# volumes.net
KiCad netlist of a schematic drawn in Altium Designer
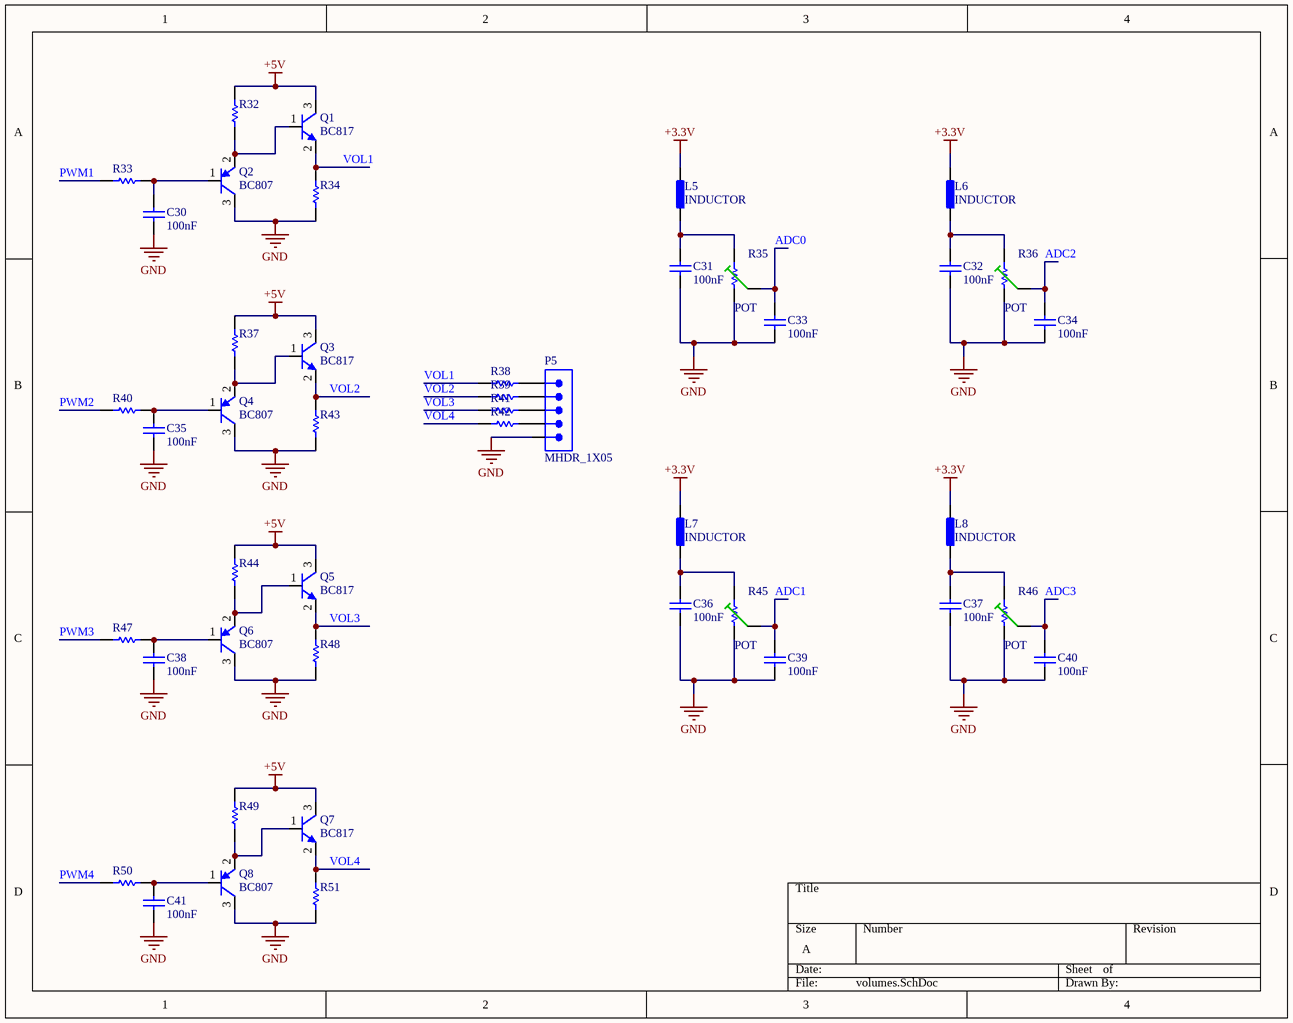
[diagram p0: volumes.SchDoc]

(export (version "E")
  (design (tool "Eeschema 10.0.6"))
  (components
    (comp (ref "C30")
      (value "100nF")
      (footprint "CAPC3216M (1206)")
      (description "Bipolar Capacitor")
      (fields
        (field (name "VOLTAGE") "100V")
        (field (name "DESIGNER") "Eng. Saeid Jorablo")
        (field (name "PUBLISHER") "SJ Unlimited")
      )
      (libsource (lib "SJ Passive Components") (part "CAP_Bipolar"))
    )
    (comp (ref "C31")
      (value "100nF")
      (footprint "CAPC3216M (1206)")
      (description "Bipolar Capacitor")
      (fields
        (field (name "VOLTAGE") "100V")
        (field (name "DESIGNER") "Eng. Saeid Jorablo")
        (field (name "PUBLISHER") "SJ Unlimited")
      )
      (libsource (lib "SJ Passive Components") (part "CAP_Bipolar"))
    )
    (comp (ref "C32")
      (value "100nF")
      (footprint "CAPC3216M (1206)")
      (description "Bipolar Capacitor")
      (fields
        (field (name "VOLTAGE") "100V")
        (field (name "DESIGNER") "Eng. Saeid Jorablo")
        (field (name "PUBLISHER") "SJ Unlimited")
      )
      (libsource (lib "SJ Passive Components") (part "CAP_Bipolar"))
    )
    (comp (ref "C33")
      (value "100nF")
      (footprint "CAPC3216M (1206)")
      (description "Bipolar Capacitor")
      (fields
        (field (name "VOLTAGE") "100V")
        (field (name "DESIGNER") "Eng. Saeid Jorablo")
        (field (name "PUBLISHER") "SJ Unlimited")
      )
      (libsource (lib "SJ Passive Components") (part "CAP_Bipolar"))
    )
    (comp (ref "C34")
      (value "100nF")
      (footprint "CAPC3216M (1206)")
      (description "Bipolar Capacitor")
      (fields
        (field (name "VOLTAGE") "100V")
        (field (name "DESIGNER") "Eng. Saeid Jorablo")
        (field (name "PUBLISHER") "SJ Unlimited")
      )
      (libsource (lib "SJ Passive Components") (part "CAP_Bipolar"))
    )
    (comp (ref "C35")
      (value "100nF")
      (footprint "CAPC3216M (1206)")
      (description "Bipolar Capacitor")
      (fields
        (field (name "VOLTAGE") "100V")
        (field (name "DESIGNER") "Eng. Saeid Jorablo")
        (field (name "PUBLISHER") "SJ Unlimited")
      )
      (libsource (lib "SJ Passive Components") (part "CAP_Bipolar"))
    )
    (comp (ref "C36")
      (value "100nF")
      (footprint "CAPC3216M (1206)")
      (description "Bipolar Capacitor")
      (fields
        (field (name "VOLTAGE") "100V")
        (field (name "DESIGNER") "Eng. Saeid Jorablo")
        (field (name "PUBLISHER") "SJ Unlimited")
      )
      (libsource (lib "SJ Passive Components") (part "CAP_Bipolar"))
    )
    (comp (ref "C37")
      (value "100nF")
      (footprint "CAPC3216M (1206)")
      (description "Bipolar Capacitor")
      (fields
        (field (name "VOLTAGE") "100V")
        (field (name "DESIGNER") "Eng. Saeid Jorablo")
        (field (name "PUBLISHER") "SJ Unlimited")
      )
      (libsource (lib "SJ Passive Components") (part "CAP_Bipolar"))
    )
    (comp (ref "C38")
      (value "100nF")
      (footprint "CAPC3216M (1206)")
      (description "Bipolar Capacitor")
      (fields
        (field (name "VOLTAGE") "100V")
        (field (name "DESIGNER") "Eng. Saeid Jorablo")
        (field (name "PUBLISHER") "SJ Unlimited")
      )
      (libsource (lib "SJ Passive Components") (part "CAP_Bipolar"))
    )
    (comp (ref "C39")
      (value "100nF")
      (footprint "CAPC3216M (1206)")
      (description "Bipolar Capacitor")
      (fields
        (field (name "VOLTAGE") "100V")
        (field (name "DESIGNER") "Eng. Saeid Jorablo")
        (field (name "PUBLISHER") "SJ Unlimited")
      )
      (libsource (lib "SJ Passive Components") (part "CAP_Bipolar"))
    )
    (comp (ref "C40")
      (value "100nF")
      (footprint "CAPC3216M (1206)")
      (description "Bipolar Capacitor")
      (fields
        (field (name "VOLTAGE") "100V")
        (field (name "DESIGNER") "Eng. Saeid Jorablo")
        (field (name "PUBLISHER") "SJ Unlimited")
      )
      (libsource (lib "SJ Passive Components") (part "CAP_Bipolar"))
    )
    (comp (ref "C41")
      (value "100nF")
      (footprint "CAPC3216M (1206)")
      (description "Bipolar Capacitor")
      (fields
        (field (name "VOLTAGE") "100V")
        (field (name "DESIGNER") "Eng. Saeid Jorablo")
        (field (name "PUBLISHER") "SJ Unlimited")
      )
      (libsource (lib "SJ Passive Components") (part "CAP_Bipolar"))
    )
    (comp (ref "L5")
      (value "INDUCTOR")
      (footprint "INDC3216")
      (description "Inductor")
      (fields (field (name "PUBLISHER") "SJ Unlimited") (field (name "DESIGNER") "Eng. Saeid Jorablo"))
      (libsource (lib "SJ Passive Components") (part "INDUCTOR"))
    )
    (comp (ref "L6")
      (value "INDUCTOR")
      (footprint "INDC3216")
      (description "Inductor")
      (fields (field (name "PUBLISHER") "SJ Unlimited") (field (name "DESIGNER") "Eng. Saeid Jorablo"))
      (libsource (lib "SJ Passive Components") (part "INDUCTOR"))
    )
    (comp (ref "L7")
      (value "INDUCTOR")
      (footprint "INDC3216")
      (description "Inductor")
      (fields (field (name "PUBLISHER") "SJ Unlimited") (field (name "DESIGNER") "Eng. Saeid Jorablo"))
      (libsource (lib "SJ Passive Components") (part "INDUCTOR"))
    )
    (comp (ref "L8")
      (value "INDUCTOR")
      (footprint "INDC3216")
      (description "Inductor")
      (fields (field (name "PUBLISHER") "SJ Unlimited") (field (name "DESIGNER") "Eng. Saeid Jorablo"))
      (libsource (lib "SJ Passive Components") (part "INDUCTOR"))
    )
    (comp (ref "P5")
      (value "MHDR_1X05")
      (footprint "MHDR1X05-254P")
      (description "Male Header 1X05")
      (libsource (lib "SJ Sockets & Connectors") (part "MHDR_1X05"))
    )
    (comp (ref "Q1")
      (value "BC817")
      (footprint "SOT23_BEC_M")
      (description "NPN Bipolar Transistor")
      (fields (field (name "PUBLISHER") "SJ Unlimited") (field (name "DESIGNER") "Eng. Saeid Jorablo"))
      (libsource (lib "SJ Passive Components") (part "NPN_BEC"))
    )
    (comp (ref "Q2")
      (value "BC807")
      (footprint "SOT23_BEC_M")
      (description "PNP Bipolar Transistor")
      (fields (field (name "PUBLISHER") "SJ Unlimited") (field (name "DESIGNER") "Eng. Saeid Jorablo"))
      (libsource (lib "SJ Passive Components") (part "PNP_BEC"))
    )
    (comp (ref "Q3")
      (value "BC817")
      (footprint "SOT23_BEC_M")
      (description "NPN Bipolar Transistor")
      (fields (field (name "PUBLISHER") "SJ Unlimited") (field (name "DESIGNER") "Eng. Saeid Jorablo"))
      (libsource (lib "SJ Passive Components") (part "NPN_BEC"))
    )
    (comp (ref "Q4")
      (value "BC807")
      (footprint "SOT23_BEC_M")
      (description "PNP Bipolar Transistor")
      (fields (field (name "PUBLISHER") "SJ Unlimited") (field (name "DESIGNER") "Eng. Saeid Jorablo"))
      (libsource (lib "SJ Passive Components") (part "PNP_BEC"))
    )
    (comp (ref "Q5")
      (value "BC817")
      (footprint "SOT23_BEC_M")
      (description "NPN Bipolar Transistor")
      (fields (field (name "PUBLISHER") "SJ Unlimited") (field (name "DESIGNER") "Eng. Saeid Jorablo"))
      (libsource (lib "SJ Passive Components") (part "NPN_BEC"))
    )
    (comp (ref "Q6")
      (value "BC807")
      (footprint "SOT23_BEC_M")
      (description "PNP Bipolar Transistor")
      (fields (field (name "PUBLISHER") "SJ Unlimited") (field (name "DESIGNER") "Eng. Saeid Jorablo"))
      (libsource (lib "SJ Passive Components") (part "PNP_BEC"))
    )
    (comp (ref "Q7")
      (value "BC817")
      (footprint "SOT23_BEC_M")
      (description "NPN Bipolar Transistor")
      (fields (field (name "PUBLISHER") "SJ Unlimited") (field (name "DESIGNER") "Eng. Saeid Jorablo"))
      (libsource (lib "SJ Passive Components") (part "NPN_BEC"))
    )
    (comp (ref "Q8")
      (value "BC807")
      (footprint "SOT23_BEC_M")
      (description "PNP Bipolar Transistor")
      (fields (field (name "PUBLISHER") "SJ Unlimited") (field (name "DESIGNER") "Eng. Saeid Jorablo"))
      (libsource (lib "SJ Passive Components") (part "PNP_BEC"))
    )
    (comp (ref "R32")
      (value "1K")
      (footprint "RESC3216X60M (1206)")
      (description "Resistor")
      (fields
        (field (name "TOLERANCE") "5%")
        (field (name "POWER") "1/8 W")
        (field (name "DESIGNER") "Eng. Saeid Jorablo")
        (field (name "PUBLISHER") "SJ Unlimited")
      )
      (libsource (lib "SJ Passive Components") (part "RES"))
    )
    (comp (ref "R33")
      (value "1K")
      (footprint "RESC3216X60M (1206)")
      (description "Resistor")
      (fields
        (field (name "TOLERANCE") "5%")
        (field (name "POWER") "1/8 W")
        (field (name "DESIGNER") "Eng. Saeid Jorablo")
        (field (name "PUBLISHER") "SJ Unlimited")
      )
      (libsource (lib "SJ Passive Components") (part "RES"))
    )
    (comp (ref "R34")
      (value "1K")
      (footprint "RESC3216X60M (1206)")
      (description "Resistor")
      (fields
        (field (name "TOLERANCE") "5%")
        (field (name "POWER") "1/8 W")
        (field (name "DESIGNER") "Eng. Saeid Jorablo")
        (field (name "PUBLISHER") "SJ Unlimited")
      )
      (libsource (lib "SJ Passive Components") (part "RES"))
    )
    (comp (ref "R35")
      (value "POT")
      (footprint "EVUF")
      (libsource (lib "SJ Passive Components") (part "RES_POT_LIN"))
    )
    (comp (ref "R36")
      (value "POT")
      (footprint "EVUF")
      (libsource (lib "SJ Passive Components") (part "RES_POT_LIN"))
    )
    (comp (ref "R37")
      (value "1K")
      (footprint "RESC3216X60M (1206)")
      (description "Resistor")
      (fields
        (field (name "TOLERANCE") "5%")
        (field (name "POWER") "1/8 W")
        (field (name "DESIGNER") "Eng. Saeid Jorablo")
        (field (name "PUBLISHER") "SJ Unlimited")
      )
      (libsource (lib "SJ Passive Components") (part "RES"))
    )
    (comp (ref "R38")
      (value "1K")
      (footprint "RESC3216X60M (1206)")
      (description "Resistor")
      (fields
        (field (name "TOLERANCE") "5%")
        (field (name "POWER") "1/8 W")
        (field (name "DESIGNER") "Eng. Saeid Jorablo")
        (field (name "PUBLISHER") "SJ Unlimited")
      )
      (libsource (lib "SJ Passive Components") (part "RES"))
    )
    (comp (ref "R39")
      (value "1K")
      (footprint "RESC3216X60M (1206)")
      (description "Resistor")
      (fields
        (field (name "TOLERANCE") "5%")
        (field (name "POWER") "1/8 W")
        (field (name "DESIGNER") "Eng. Saeid Jorablo")
        (field (name "PUBLISHER") "SJ Unlimited")
      )
      (libsource (lib "SJ Passive Components") (part "RES"))
    )
    (comp (ref "R40")
      (value "1K")
      (footprint "RESC3216X60M (1206)")
      (description "Resistor")
      (fields
        (field (name "TOLERANCE") "5%")
        (field (name "POWER") "1/8 W")
        (field (name "DESIGNER") "Eng. Saeid Jorablo")
        (field (name "PUBLISHER") "SJ Unlimited")
      )
      (libsource (lib "SJ Passive Components") (part "RES"))
    )
    (comp (ref "R41")
      (value "1K")
      (footprint "RESC3216X60M (1206)")
      (description "Resistor")
      (fields
        (field (name "TOLERANCE") "5%")
        (field (name "POWER") "1/8 W")
        (field (name "DESIGNER") "Eng. Saeid Jorablo")
        (field (name "PUBLISHER") "SJ Unlimited")
      )
      (libsource (lib "SJ Passive Components") (part "RES"))
    )
    (comp (ref "R42")
      (value "1K")
      (footprint "RESC3216X60M (1206)")
      (description "Resistor")
      (fields
        (field (name "TOLERANCE") "5%")
        (field (name "POWER") "1/8 W")
        (field (name "DESIGNER") "Eng. Saeid Jorablo")
        (field (name "PUBLISHER") "SJ Unlimited")
      )
      (libsource (lib "SJ Passive Components") (part "RES"))
    )
    (comp (ref "R43")
      (value "1K")
      (footprint "RESC3216X60M (1206)")
      (description "Resistor")
      (fields
        (field (name "TOLERANCE") "5%")
        (field (name "POWER") "1/8 W")
        (field (name "DESIGNER") "Eng. Saeid Jorablo")
        (field (name "PUBLISHER") "SJ Unlimited")
      )
      (libsource (lib "SJ Passive Components") (part "RES"))
    )
    (comp (ref "R44")
      (value "1K")
      (footprint "RESC3216X60M (1206)")
      (description "Resistor")
      (fields
        (field (name "TOLERANCE") "5%")
        (field (name "POWER") "1/8 W")
        (field (name "DESIGNER") "Eng. Saeid Jorablo")
        (field (name "PUBLISHER") "SJ Unlimited")
      )
      (libsource (lib "SJ Passive Components") (part "RES"))
    )
    (comp (ref "R45")
      (value "POT")
      (footprint "EVUF")
      (libsource (lib "SJ Passive Components") (part "RES_POT_LIN"))
    )
    (comp (ref "R46")
      (value "POT")
      (footprint "EVUF")
      (libsource (lib "SJ Passive Components") (part "RES_POT_LIN"))
    )
    (comp (ref "R47")
      (value "1K")
      (footprint "RESC3216X60M (1206)")
      (description "Resistor")
      (fields
        (field (name "TOLERANCE") "5%")
        (field (name "POWER") "1/8 W")
        (field (name "DESIGNER") "Eng. Saeid Jorablo")
        (field (name "PUBLISHER") "SJ Unlimited")
      )
      (libsource (lib "SJ Passive Components") (part "RES"))
    )
    (comp (ref "R48")
      (value "1K")
      (footprint "RESC3216X60M (1206)")
      (description "Resistor")
      (fields
        (field (name "TOLERANCE") "5%")
        (field (name "POWER") "1/8 W")
        (field (name "DESIGNER") "Eng. Saeid Jorablo")
        (field (name "PUBLISHER") "SJ Unlimited")
      )
      (libsource (lib "SJ Passive Components") (part "RES"))
    )
    (comp (ref "R49")
      (value "1K")
      (footprint "RESC3216X60M (1206)")
      (description "Resistor")
      (fields
        (field (name "TOLERANCE") "5%")
        (field (name "POWER") "1/8 W")
        (field (name "DESIGNER") "Eng. Saeid Jorablo")
        (field (name "PUBLISHER") "SJ Unlimited")
      )
      (libsource (lib "SJ Passive Components") (part "RES"))
    )
    (comp (ref "R50")
      (value "1K")
      (footprint "RESC3216X60M (1206)")
      (description "Resistor")
      (fields
        (field (name "TOLERANCE") "5%")
        (field (name "POWER") "1/8 W")
        (field (name "DESIGNER") "Eng. Saeid Jorablo")
        (field (name "PUBLISHER") "SJ Unlimited")
      )
      (libsource (lib "SJ Passive Components") (part "RES"))
    )
    (comp (ref "R51")
      (value "1K")
      (footprint "RESC3216X60M (1206)")
      (description "Resistor")
      (fields
        (field (name "TOLERANCE") "5%")
        (field (name "POWER") "1/8 W")
        (field (name "DESIGNER") "Eng. Saeid Jorablo")
        (field (name "PUBLISHER") "SJ Unlimited")
      )
      (libsource (lib "SJ Passive Components") (part "RES"))
    )
  )
  (nets
    (net (code "1") (name "+3.3V") (class "Default")
      (node (ref "L5") (pin "2") (pinfunction "2_2") (pintype "passive"))
      (node (ref "L6") (pin "2") (pinfunction "2_2") (pintype "passive"))
      (node (ref "L7") (pin "2") (pinfunction "2_2") (pintype "passive"))
      (node (ref "L8") (pin "2") (pinfunction "2_2") (pintype "passive"))
    )
    (net (code "2") (name "+5V") (class "Default")
      (node (ref "Q1") (pin "3") (pinfunction "C_3") (pintype "passive"))
      (node (ref "Q3") (pin "3") (pinfunction "C_3") (pintype "passive"))
      (node (ref "Q5") (pin "3") (pinfunction "C_3") (pintype "passive"))
      (node (ref "Q7") (pin "3") (pinfunction "C_3") (pintype "passive"))
      (node (ref "R32") (pin "1") (pinfunction "1_1") (pintype "passive"))
      (node (ref "R37") (pin "1") (pinfunction "1_1") (pintype "passive"))
      (node (ref "R44") (pin "1") (pinfunction "1_1") (pintype "passive"))
      (node (ref "R49") (pin "1") (pinfunction "1_1") (pintype "passive"))
    )
    (net (code "3") (name "/ADC0") (class "Default")
      (node (ref "C33") (pin "1") (pinfunction "+_1") (pintype "passive"))
      (node (ref "R35") (pin "2") (pinfunction "WIPER_2") (pintype "passive"))
    )
    (net (code "4") (name "/ADC1") (class "Default")
      (node (ref "C39") (pin "1") (pinfunction "+_1") (pintype "passive"))
      (node (ref "R45") (pin "2") (pinfunction "WIPER_2") (pintype "passive"))
    )
    (net (code "5") (name "/ADC2") (class "Default")
      (node (ref "C34") (pin "1") (pinfunction "+_1") (pintype "passive"))
      (node (ref "R36") (pin "2") (pinfunction "WIPER_2") (pintype "passive"))
    )
    (net (code "6") (name "/ADC3") (class "Default")
      (node (ref "C40") (pin "1") (pinfunction "+_1") (pintype "passive"))
      (node (ref "R46") (pin "2") (pinfunction "WIPER_2") (pintype "passive"))
    )
    (net (code "7") (name "/PWM1") (class "Default")
      (node (ref "R33") (pin "2") (pinfunction "2_2") (pintype "passive"))
    )
    (net (code "8") (name "/PWM2") (class "Default")
      (node (ref "R40") (pin "2") (pinfunction "2_2") (pintype "passive"))
    )
    (net (code "9") (name "/PWM3") (class "Default")
      (node (ref "R47") (pin "2") (pinfunction "2_2") (pintype "passive"))
    )
    (net (code "10") (name "/PWM4") (class "Default")
      (node (ref "R50") (pin "2") (pinfunction "2_2") (pintype "passive"))
    )
    (net (code "11") (name "/VOL1") (class "Default")
      (node (ref "Q1") (pin "2") (pinfunction "E_2") (pintype "passive"))
      (node (ref "R34") (pin "1") (pinfunction "1_1") (pintype "passive"))
      (node (ref "R38") (pin "2") (pinfunction "2_2") (pintype "passive"))
    )
    (net (code "12") (name "/VOL2") (class "Default")
      (node (ref "Q3") (pin "2") (pinfunction "E_2") (pintype "passive"))
      (node (ref "R39") (pin "2") (pinfunction "2_2") (pintype "passive"))
      (node (ref "R43") (pin "1") (pinfunction "1_1") (pintype "passive"))
    )
    (net (code "13") (name "/VOL3") (class "Default")
      (node (ref "Q5") (pin "2") (pinfunction "E_2") (pintype "passive"))
      (node (ref "R41") (pin "2") (pinfunction "2_2") (pintype "passive"))
      (node (ref "R48") (pin "1") (pinfunction "1_1") (pintype "passive"))
    )
    (net (code "14") (name "/VOL4") (class "Default")
      (node (ref "Q7") (pin "2") (pinfunction "E_2") (pintype "passive"))
      (node (ref "R42") (pin "2") (pinfunction "2_2") (pintype "passive"))
      (node (ref "R51") (pin "1") (pinfunction "1_1") (pintype "passive"))
    )
    (net (code "15") (name "GND") (class "Default")
      (node (ref "C30") (pin "2") (pinfunction "-_2") (pintype "passive"))
      (node (ref "C31") (pin "2") (pinfunction "-_2") (pintype "passive"))
      (node (ref "C32") (pin "2") (pinfunction "-_2") (pintype "passive"))
      (node (ref "C33") (pin "2") (pinfunction "-_2") (pintype "passive"))
      (node (ref "C34") (pin "2") (pinfunction "-_2") (pintype "passive"))
      (node (ref "C35") (pin "2") (pinfunction "-_2") (pintype "passive"))
      (node (ref "C36") (pin "2") (pinfunction "-_2") (pintype "passive"))
      (node (ref "C37") (pin "2") (pinfunction "-_2") (pintype "passive"))
      (node (ref "C38") (pin "2") (pinfunction "-_2") (pintype "passive"))
      (node (ref "C39") (pin "2") (pinfunction "-_2") (pintype "passive"))
      (node (ref "C40") (pin "2") (pinfunction "-_2") (pintype "passive"))
      (node (ref "C41") (pin "2") (pinfunction "-_2") (pintype "passive"))
      (node (ref "P5") (pin "5") (pinfunction "5_5") (pintype "passive"))
      (node (ref "Q2") (pin "3") (pinfunction "C_3") (pintype "passive"))
      (node (ref "Q4") (pin "3") (pinfunction "C_3") (pintype "passive"))
      (node (ref "Q6") (pin "3") (pinfunction "C_3") (pintype "passive"))
      (node (ref "Q8") (pin "3") (pinfunction "C_3") (pintype "passive"))
      (node (ref "R34") (pin "2") (pinfunction "2_2") (pintype "passive"))
      (node (ref "R35") (pin "3") (pinfunction "CW_3") (pintype "passive"))
      (node (ref "R36") (pin "3") (pinfunction "CW_3") (pintype "passive"))
      (node (ref "R43") (pin "2") (pinfunction "2_2") (pintype "passive"))
      (node (ref "R45") (pin "3") (pinfunction "CW_3") (pintype "passive"))
      (node (ref "R46") (pin "3") (pinfunction "CW_3") (pintype "passive"))
      (node (ref "R48") (pin "2") (pinfunction "2_2") (pintype "passive"))
      (node (ref "R51") (pin "2") (pinfunction "2_2") (pintype "passive"))
    )
    (net (code "16") (name "Net-(C30-+)") (class "Default")
      (node (ref "C30") (pin "1") (pinfunction "+_1") (pintype "passive"))
      (node (ref "Q2") (pin "1") (pinfunction "B_1") (pintype "passive"))
      (node (ref "R33") (pin "1") (pinfunction "1_1") (pintype "passive"))
    )
    (net (code "17") (name "Net-(C31-+)") (class "Default")
      (node (ref "C31") (pin "1") (pinfunction "+_1") (pintype "passive"))
      (node (ref "L5") (pin "1") (pinfunction "1_1") (pintype "passive"))
      (node (ref "R35") (pin "1") (pinfunction "CCW_1") (pintype "passive"))
    )
    (net (code "18") (name "Net-(C32-+)") (class "Default")
      (node (ref "C32") (pin "1") (pinfunction "+_1") (pintype "passive"))
      (node (ref "L6") (pin "1") (pinfunction "1_1") (pintype "passive"))
      (node (ref "R36") (pin "1") (pinfunction "CCW_1") (pintype "passive"))
    )
    (net (code "19") (name "Net-(C35-+)") (class "Default")
      (node (ref "C35") (pin "1") (pinfunction "+_1") (pintype "passive"))
      (node (ref "Q4") (pin "1") (pinfunction "B_1") (pintype "passive"))
      (node (ref "R40") (pin "1") (pinfunction "1_1") (pintype "passive"))
    )
    (net (code "20") (name "Net-(C36-+)") (class "Default")
      (node (ref "C36") (pin "1") (pinfunction "+_1") (pintype "passive"))
      (node (ref "L7") (pin "1") (pinfunction "1_1") (pintype "passive"))
      (node (ref "R45") (pin "1") (pinfunction "CCW_1") (pintype "passive"))
    )
    (net (code "21") (name "Net-(C37-+)") (class "Default")
      (node (ref "C37") (pin "1") (pinfunction "+_1") (pintype "passive"))
      (node (ref "L8") (pin "1") (pinfunction "1_1") (pintype "passive"))
      (node (ref "R46") (pin "1") (pinfunction "CCW_1") (pintype "passive"))
    )
    (net (code "22") (name "Net-(C38-+)") (class "Default")
      (node (ref "C38") (pin "1") (pinfunction "+_1") (pintype "passive"))
      (node (ref "Q6") (pin "1") (pinfunction "B_1") (pintype "passive"))
      (node (ref "R47") (pin "1") (pinfunction "1_1") (pintype "passive"))
    )
    (net (code "23") (name "Net-(C41-+)") (class "Default")
      (node (ref "C41") (pin "1") (pinfunction "+_1") (pintype "passive"))
      (node (ref "Q8") (pin "1") (pinfunction "B_1") (pintype "passive"))
      (node (ref "R50") (pin "1") (pinfunction "1_1") (pintype "passive"))
    )
    (net (code "24") (name "Net-(P5-Pad1)") (class "Default")
      (node (ref "P5") (pin "1") (pinfunction "1_1") (pintype "passive"))
      (node (ref "R38") (pin "1") (pinfunction "1_1") (pintype "passive"))
    )
    (net (code "25") (name "Net-(P5-Pad2)") (class "Default")
      (node (ref "P5") (pin "2") (pinfunction "2_2") (pintype "passive"))
      (node (ref "R39") (pin "1") (pinfunction "1_1") (pintype "passive"))
    )
    (net (code "26") (name "Net-(P5-Pad3)") (class "Default")
      (node (ref "P5") (pin "3") (pinfunction "3_3") (pintype "passive"))
      (node (ref "R41") (pin "1") (pinfunction "1_1") (pintype "passive"))
    )
    (net (code "27") (name "Net-(P5-Pad4)") (class "Default")
      (node (ref "P5") (pin "4") (pinfunction "4_4") (pintype "passive"))
      (node (ref "R42") (pin "1") (pinfunction "1_1") (pintype "passive"))
    )
    (net (code "28") (name "Net-(Q1-B)") (class "Default")
      (node (ref "Q1") (pin "1") (pinfunction "B_1") (pintype "passive"))
      (node (ref "Q2") (pin "2") (pinfunction "E_2") (pintype "passive"))
      (node (ref "R32") (pin "2") (pinfunction "2_2") (pintype "passive"))
    )
    (net (code "29") (name "Net-(Q3-B)") (class "Default")
      (node (ref "Q3") (pin "1") (pinfunction "B_1") (pintype "passive"))
      (node (ref "Q4") (pin "2") (pinfunction "E_2") (pintype "passive"))
      (node (ref "R37") (pin "2") (pinfunction "2_2") (pintype "passive"))
    )
    (net (code "30") (name "Net-(Q5-B)") (class "Default")
      (node (ref "Q5") (pin "1") (pinfunction "B_1") (pintype "passive"))
      (node (ref "Q6") (pin "2") (pinfunction "E_2") (pintype "passive"))
      (node (ref "R44") (pin "2") (pinfunction "2_2") (pintype "passive"))
    )
    (net (code "31") (name "Net-(Q7-B)") (class "Default")
      (node (ref "Q7") (pin "1") (pinfunction "B_1") (pintype "passive"))
      (node (ref "Q8") (pin "2") (pinfunction "E_2") (pintype "passive"))
      (node (ref "R49") (pin "2") (pinfunction "2_2") (pintype "passive"))
    )
  )
)
